# version_0_release2.net
KiCad netlist of a schematic drawn in EAGLE
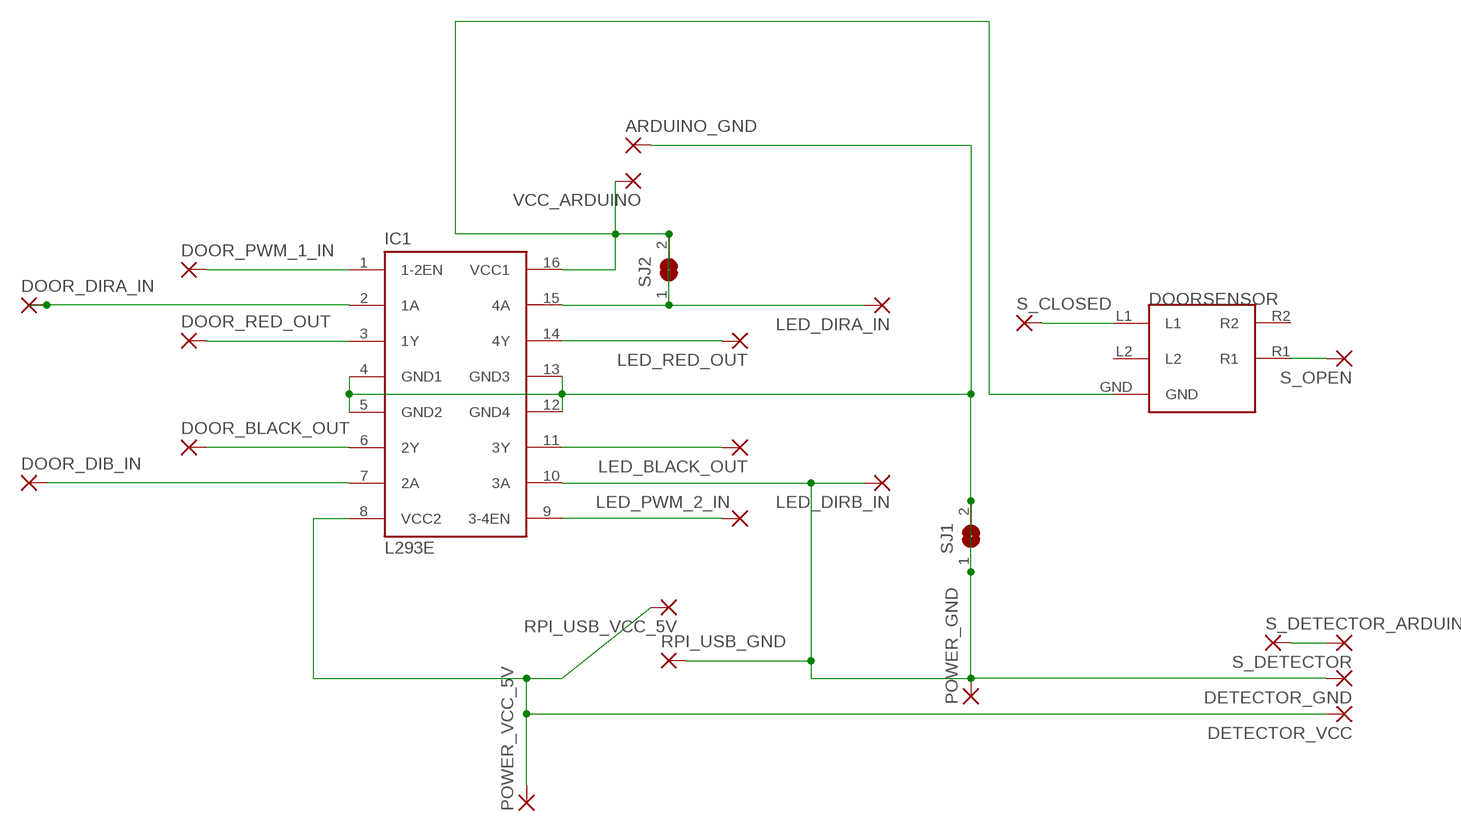
[diagram p0: schematic, sheet 1]

(export (version "E")
  (design (tool "Eeschema 10.0.6"))
  (components
    (comp (ref "ARDUINO_GND")
      (value "SMD5")
      (footprint "eagle-import:SMD2,54-5,08")
      (libsource (lib "eagle-import") (part "SMD5"))
    )
    (comp (ref "DETECTOR_GND")
      (value "SMD5")
      (footprint "eagle-import:SMD2,54-5,08")
      (libsource (lib "eagle-import") (part "SMD5"))
    )
    (comp (ref "DETECTOR_VCC")
      (value "SMD5")
      (footprint "eagle-import:SMD2,54-5,08")
      (libsource (lib "eagle-import") (part "SMD5"))
    )
    (comp (ref "DOORSENSOR")
      (value "DOORSENSOR")
      (footprint "eagle-import:DOORSENSOR")
      (libsource (lib "eagle-import") (part "DOORSENSOR"))
    )
    (comp (ref "DOOR_BLACK_OUT")
      (value "SMD5")
      (footprint "eagle-import:SMD2,54-5,08")
      (libsource (lib "eagle-import") (part "SMD5"))
    )
    (comp (ref "DOOR_DIB_IN")
      (value "SMD5")
      (footprint "eagle-import:SMD2,54-5,08")
      (libsource (lib "eagle-import") (part "SMD5"))
    )
    (comp (ref "DOOR_DIRA_IN")
      (value "SMD5")
      (footprint "eagle-import:SMD2,54-5,08")
      (libsource (lib "eagle-import") (part "SMD5"))
    )
    (comp (ref "DOOR_PWM_1_IN")
      (value "SMD5")
      (footprint "eagle-import:SMD2,54-5,08")
      (libsource (lib "eagle-import") (part "SMD5"))
    )
    (comp (ref "DOOR_RED_OUT")
      (value "SMD5")
      (footprint "eagle-import:SMD2,54-5,08")
      (libsource (lib "eagle-import") (part "SMD5"))
    )
    (comp (ref "IC1")
      (value "L293E")
      (footprint "eagle-import:DIL16")
      (fields (field (name "MF") "Arrow Electronics"))
      (libsource (lib "eagle-import") (part "L293E"))
    )
    (comp (ref "LED_BLACK_OUT")
      (value "SMD5")
      (footprint "eagle-import:SMD2,54-5,08")
      (libsource (lib "eagle-import") (part "SMD5"))
    )
    (comp (ref "LED_DIRA_IN")
      (value "SMD5")
      (footprint "eagle-import:SMD2,54-5,08")
      (libsource (lib "eagle-import") (part "SMD5"))
    )
    (comp (ref "LED_DIRB_IN")
      (value "SMD5")
      (footprint "eagle-import:SMD2,54-5,08")
      (libsource (lib "eagle-import") (part "SMD5"))
    )
    (comp (ref "LED_PWM_2_IN")
      (value "SMD5")
      (footprint "eagle-import:SMD2,54-5,08")
      (libsource (lib "eagle-import") (part "SMD5"))
    )
    (comp (ref "LED_RED_OUT")
      (value "SMD5")
      (footprint "eagle-import:SMD2,54-5,08")
      (libsource (lib "eagle-import") (part "SMD5"))
    )
    (comp (ref "POWER_GND")
      (value "SMD5")
      (footprint "eagle-import:SMD2,54-5,08")
      (libsource (lib "eagle-import") (part "SMD5"))
    )
    (comp (ref "POWER_VCC_5V")
      (value "SMD5")
      (footprint "eagle-import:SMD2,54-5,08")
      (libsource (lib "eagle-import") (part "SMD5"))
    )
    (comp (ref "RPI_USB_GND")
      (value "SMD5")
      (footprint "eagle-import:SMD2,54-5,08")
      (libsource (lib "eagle-import") (part "SMD5"))
    )
    (comp (ref "RPI_USB_VCC_5V")
      (value "SMD5")
      (footprint "eagle-import:SMD2,54-5,08")
      (libsource (lib "eagle-import") (part "SMD5"))
    )
    (comp (ref "SJ1") (value "SJ") (footprint "eagle-import:SJ") (libsource (lib "eagle-import") (part "SJ")))
    (comp (ref "SJ2") (value "SJ") (footprint "eagle-import:SJ") (libsource (lib "eagle-import") (part "SJ")))
    (comp (ref "S_CLOSED")
      (value "SMD5")
      (footprint "eagle-import:SMD2,54-5,08")
      (libsource (lib "eagle-import") (part "SMD5"))
    )
    (comp (ref "S_DETECTOR")
      (value "SMD5")
      (footprint "eagle-import:SMD2,54-5,08")
      (libsource (lib "eagle-import") (part "SMD5"))
    )
    (comp (ref "S_DETECTOR_ARDUINO")
      (value "SMD5")
      (footprint "eagle-import:SMD2,54-5,08")
      (libsource (lib "eagle-import") (part "SMD5"))
    )
    (comp (ref "S_OPEN")
      (value "SMD5")
      (footprint "eagle-import:SMD2,54-5,08")
      (libsource (lib "eagle-import") (part "SMD5"))
    )
    (comp (ref "VCC_ARDUINO")
      (value "SMD5")
      (footprint "eagle-import:SMD2,54-5,08")
      (libsource (lib "eagle-import") (part "SMD5"))
    )
  )
  (nets
    (net (code "1") (name "Net-(ARDUINO_GND-P)") (class "Default")
      (node (ref "ARDUINO_GND") (pin "1") (pinfunction "P_1") (pintype "passive"))
      (node (ref "DETECTOR_GND") (pin "1") (pinfunction "P_1") (pintype "passive"))
      (node (ref "IC1") (pin "10") (pinfunction "3A_10") (pintype "input"))
      (node (ref "IC1") (pin "12") (pinfunction "GND4_12") (pintype "power_in"))
      (node (ref "IC1") (pin "13") (pinfunction "GND3_13") (pintype "power_in"))
      (node (ref "IC1") (pin "4") (pinfunction "GND1_4") (pintype "power_in"))
      (node (ref "IC1") (pin "5") (pinfunction "GND2_5") (pintype "power_in"))
      (node (ref "LED_DIRB_IN") (pin "1") (pinfunction "P_1") (pintype "passive"))
      (node (ref "POWER_GND") (pin "1") (pinfunction "P_1") (pintype "passive"))
      (node (ref "RPI_USB_GND") (pin "1") (pinfunction "P_1") (pintype "passive"))
      (node (ref "SJ1") (pin "1") (pinfunction "1_1") (pintype "passive"))
      (node (ref "SJ1") (pin "2") (pinfunction "2_2") (pintype "passive"))
    )
    (net (code "2") (name "Net-(DETECTOR_VCC-P)") (class "Default")
      (node (ref "DETECTOR_VCC") (pin "1") (pinfunction "P_1") (pintype "passive"))
      (node (ref "IC1") (pin "8") (pinfunction "VCC2_8") (pintype "power_in"))
      (node (ref "POWER_VCC_5V") (pin "1") (pinfunction "P_1") (pintype "passive"))
      (node (ref "RPI_USB_VCC_5V") (pin "1") (pinfunction "P_1") (pintype "passive"))
    )
    (net (code "3") (name "Net-(DOOR_BLACK_OUT-P)") (class "Default")
      (node (ref "DOOR_BLACK_OUT") (pin "1") (pinfunction "P_1") (pintype "passive"))
      (node (ref "IC1") (pin "6") (pinfunction "2Y_6") (pintype "output"))
    )
    (net (code "4") (name "Net-(DOOR_DIB_IN-P)") (class "Default")
      (node (ref "DOOR_DIB_IN") (pin "1") (pinfunction "P_1") (pintype "passive"))
      (node (ref "IC1") (pin "7") (pinfunction "2A_7") (pintype "input"))
    )
    (net (code "5") (name "Net-(DOOR_DIRA_IN-P)") (class "Default")
      (node (ref "DOOR_DIRA_IN") (pin "1") (pinfunction "P_1") (pintype "passive"))
      (node (ref "IC1") (pin "2") (pinfunction "1A_2") (pintype "input"))
    )
    (net (code "6") (name "Net-(DOOR_PWM_1_IN-P)") (class "Default")
      (node (ref "DOOR_PWM_1_IN") (pin "1") (pinfunction "P_1") (pintype "passive"))
      (node (ref "IC1") (pin "1") (pinfunction "1-2EN_1") (pintype "input"))
    )
    (net (code "7") (name "Net-(DOOR_RED_OUT-P)") (class "Default")
      (node (ref "DOOR_RED_OUT") (pin "1") (pinfunction "P_1") (pintype "passive"))
      (node (ref "IC1") (pin "3") (pinfunction "1Y_3") (pintype "output"))
    )
    (net (code "8") (name "Net-(IC1-3-4EN)") (class "Default")
      (node (ref "IC1") (pin "9") (pinfunction "3-4EN_9") (pintype "input"))
      (node (ref "LED_PWM_2_IN") (pin "1") (pinfunction "P_1") (pintype "passive"))
    )
    (net (code "9") (name "Net-(IC1-3Y)") (class "Default")
      (node (ref "IC1") (pin "11") (pinfunction "3Y_11") (pintype "output"))
      (node (ref "LED_BLACK_OUT") (pin "1") (pinfunction "P_1") (pintype "passive"))
    )
    (net (code "10") (name "Net-(IC1-4A)") (class "Default")
      (node (ref "DOORSENSOR") (pin "GND") (pinfunction "GND_GND") (pintype "bidirectional"))
      (node (ref "IC1") (pin "15") (pinfunction "4A_15") (pintype "input"))
      (node (ref "IC1") (pin "16") (pinfunction "VCC1_16") (pintype "power_in"))
      (node (ref "LED_DIRA_IN") (pin "1") (pinfunction "P_1") (pintype "passive"))
      (node (ref "SJ2") (pin "1") (pinfunction "1_1") (pintype "passive"))
      (node (ref "SJ2") (pin "2") (pinfunction "2_2") (pintype "passive"))
      (node (ref "VCC_ARDUINO") (pin "1") (pinfunction "P_1") (pintype "passive"))
    )
    (net (code "11") (name "Net-(IC1-4Y)") (class "Default")
      (node (ref "IC1") (pin "14") (pinfunction "4Y_14") (pintype "output"))
      (node (ref "LED_RED_OUT") (pin "1") (pinfunction "P_1") (pintype "passive"))
    )
    (net (code "12") (name "Net-(S_CLOSED-P)") (class "Default")
      (node (ref "DOORSENSOR") (pin "L1") (pinfunction "L1_L1") (pintype "bidirectional"))
      (node (ref "S_CLOSED") (pin "1") (pinfunction "P_1") (pintype "passive"))
    )
    (net (code "13") (name "Net-(S_DETECTOR-P)") (class "Default")
      (node (ref "S_DETECTOR") (pin "1") (pinfunction "P_1") (pintype "passive"))
      (node (ref "S_DETECTOR_ARDUINO") (pin "1") (pinfunction "P_1") (pintype "passive"))
    )
    (net (code "14") (name "Net-(S_OPEN-P)") (class "Default")
      (node (ref "DOORSENSOR") (pin "R1") (pinfunction "R1_R1") (pintype "bidirectional"))
      (node (ref "S_OPEN") (pin "1") (pinfunction "P_1") (pintype "passive"))
    )
    (net (code "15") (name "unconnected-(DOORSENSOR-PadL2)") (class "Default")
      (node (ref "DOORSENSOR") (pin "L2") (pinfunction "L2_L2") (pintype "bidirectional"))
    )
    (net (code "16") (name "unconnected-(DOORSENSOR-PadR2)") (class "Default")
      (node (ref "DOORSENSOR") (pin "R2") (pinfunction "R2_R2") (pintype "bidirectional"))
    )
  )
)
